# Sheet2.net
KiCad netlist of a schematic drawn in Altium Designer
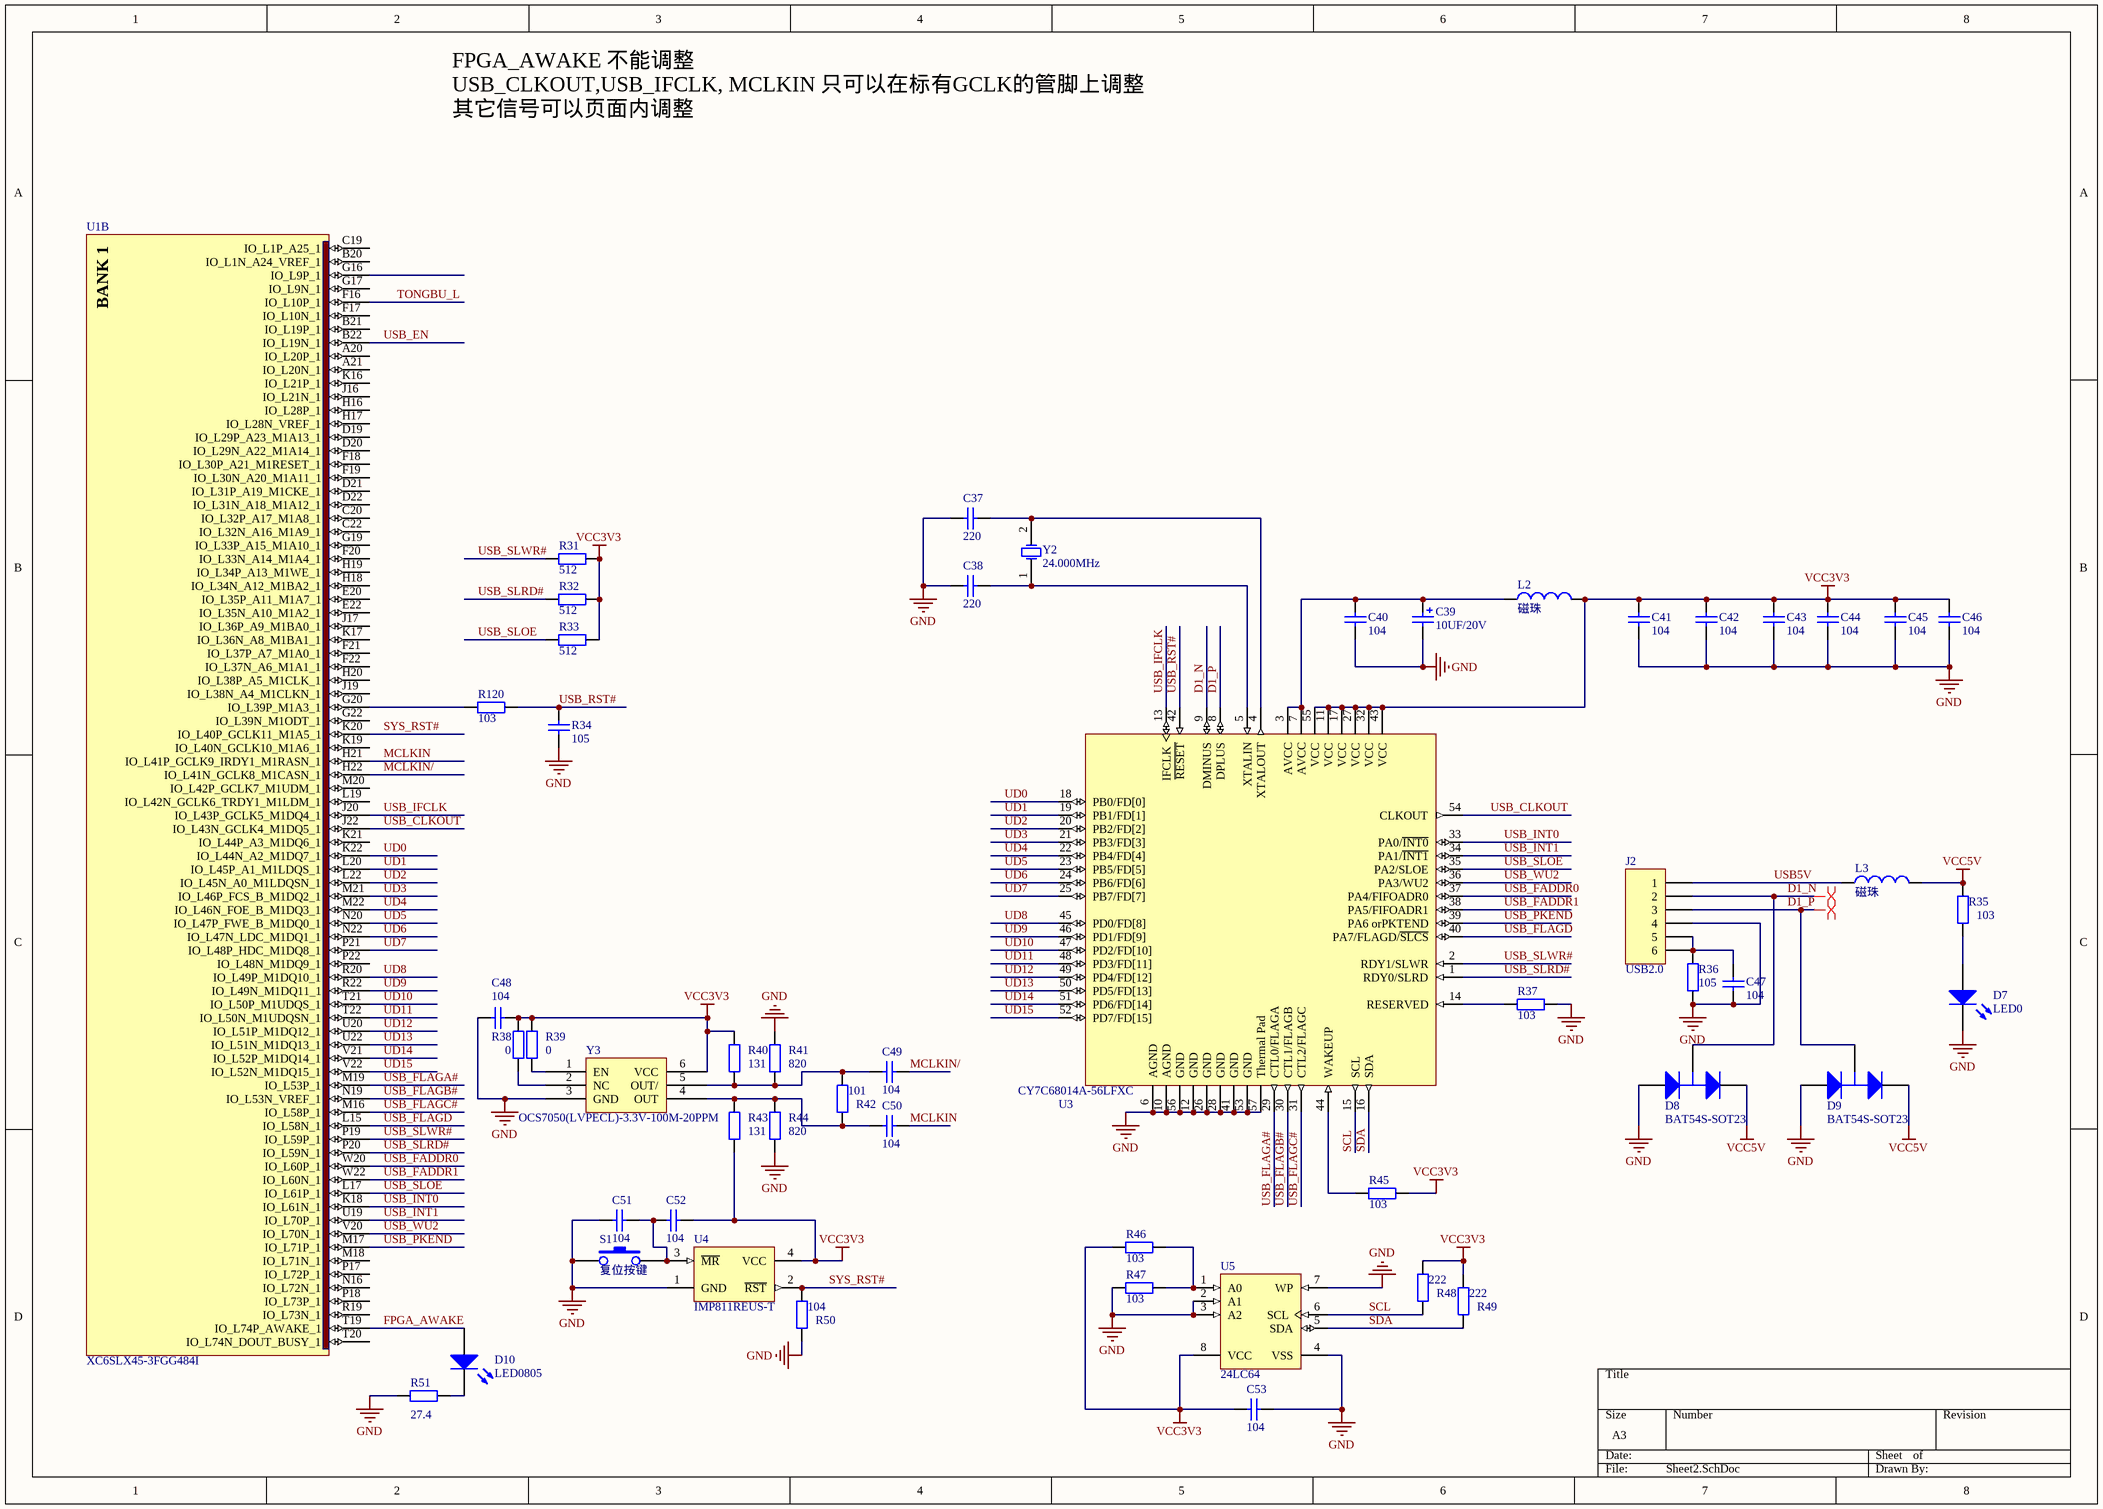
[diagram p0: Sheet2.SchDoc]

(export (version "E")
  (design (tool "Eeschema 10.0.6"))
  (components
    (comp (ref "C37")
      (value "220")
      (footprint "0402")
      (description "Capacitor")
      (fields (field (name "PUBLISHER") "Altium Limited"))
      (libsource (lib "Miscellaneous Devices") (part "Cap"))
    )
    (comp (ref "C38")
      (value "220")
      (footprint "0402")
      (description "Capacitor")
      (fields (field (name "PUBLISHER") "Altium Limited"))
      (libsource (lib "Miscellaneous Devices") (part "Cap"))
    )
    (comp (ref "C39")
      (value "10UF/20V")
      (footprint "CAP-B")
      (description "Polarized Capacitor (Axial)")
      (fields (field (name "PUBLISHER") "Altium Limited"))
      (libsource (lib "Miscellaneous Devices") (part "Cap Pol2"))
    )
    (comp (ref "C40")
      (value "104")
      (footprint "0402")
      (description "Capacitor")
      (fields (field (name "PUBLISHER") "Altium Limited"))
      (libsource (lib "Miscellaneous Devices") (part "Cap"))
    )
    (comp (ref "C41")
      (value "104")
      (footprint "0402")
      (description "Capacitor")
      (fields (field (name "PUBLISHER") "Altium Limited"))
      (libsource (lib "Miscellaneous Devices") (part "Cap"))
    )
    (comp (ref "C42")
      (value "104")
      (footprint "0402")
      (description "Capacitor")
      (fields (field (name "PUBLISHER") "Altium Limited"))
      (libsource (lib "Miscellaneous Devices") (part "Cap"))
    )
    (comp (ref "C43")
      (value "104")
      (footprint "0402")
      (description "Capacitor")
      (fields (field (name "PUBLISHER") "Altium Limited"))
      (libsource (lib "Miscellaneous Devices") (part "Cap"))
    )
    (comp (ref "C44")
      (value "104")
      (footprint "0402")
      (description "Capacitor")
      (fields (field (name "PUBLISHER") "Altium Limited"))
      (libsource (lib "Miscellaneous Devices") (part "Cap"))
    )
    (comp (ref "C45")
      (value "104")
      (footprint "0402")
      (description "Capacitor")
      (fields (field (name "PUBLISHER") "Altium Limited"))
      (libsource (lib "Miscellaneous Devices") (part "Cap"))
    )
    (comp (ref "C46")
      (value "104")
      (footprint "0402")
      (description "Capacitor")
      (fields (field (name "PUBLISHER") "Altium Limited"))
      (libsource (lib "Miscellaneous Devices") (part "Cap"))
    )
    (comp (ref "C47")
      (value "104")
      (footprint "0402")
      (description "Capacitor")
      (fields (field (name "PUBLISHER") "Altium Limited"))
      (libsource (lib "Miscellaneous Devices") (part "Cap"))
    )
    (comp (ref "C48")
      (value "104")
      (footprint "0402")
      (description "Capacitor")
      (fields (field (name "PUBLISHER") "Altium Limited"))
      (libsource (lib "Miscellaneous Devices") (part "Cap"))
    )
    (comp (ref "C49")
      (value "104")
      (footprint "0402")
      (description "Capacitor")
      (fields (field (name "PUBLISHER") "Altium Limited"))
      (libsource (lib "Miscellaneous Devices") (part "Cap"))
    )
    (comp (ref "C50")
      (value "104")
      (footprint "0402")
      (description "Capacitor")
      (fields (field (name "PUBLISHER") "Altium Limited"))
      (libsource (lib "Miscellaneous Devices") (part "Cap"))
    )
    (comp (ref "C51")
      (value "104")
      (footprint "0402")
      (description "Capacitor")
      (fields (field (name "PUBLISHER") "Altium Limited"))
      (libsource (lib "Miscellaneous Devices") (part "Cap"))
    )
    (comp (ref "C52")
      (value "104")
      (footprint "0402")
      (description "Capacitor")
      (fields (field (name "PUBLISHER") "Altium Limited"))
      (libsource (lib "Miscellaneous Devices") (part "Cap"))
    )
    (comp (ref "C53")
      (value "104")
      (footprint "0402")
      (description "Capacitor")
      (fields (field (name "PUBLISHER") "Altium Limited"))
      (libsource (lib "Miscellaneous Devices") (part "Cap"))
    )
    (comp (ref "D7")
      (value "LED0")
      (footprint "0805LED")
      (description "Typical INFRARED GaAs LED")
      (fields (field (name "PUBLISHER") "Altium Limited"))
      (libsource (lib "Miscellaneous Devices") (part "LED0"))
    )
    (comp (ref "D8")
      (value "BAT54S-SOT23")
      (footprint "SOT23-3L")
      (description "Silicon Switching Diode Array for High-Speed Switching")
      (fields (field (name "PUBLISHER") "Altium Limited"))
      (libsource (lib "Infineon Discrete Diode") (part "BAV99"))
    )
    (comp (ref "D9")
      (value "BAT54S-SOT23")
      (footprint "SOT23-3L")
      (description "Silicon Switching Diode Array for High-Speed Switching")
      (fields (field (name "PUBLISHER") "Altium Limited"))
      (libsource (lib "Infineon Discrete Diode") (part "BAV99"))
    )
    (comp (ref "D10")
      (value "LED0805")
      (footprint "0805LED")
      (description "Typical INFRARED GaAs LED")
      (fields (field (name "PUBLISHER") "Altium Limited"))
      (libsource (lib "Miscellaneous Devices") (part "LED0"))
    )
    (comp (ref "J2")
      (value "USB2.0")
      (footprint "USB-B")
      (description "Header, 6-Pin")
      (fields (field (name "PUBLISHER") "Altium Limited"))
      (libsource (lib "Miscellaneous Connectors") (part "Header 6"))
    )
    (comp (ref "L2")
      (value "磁珠")
      (footprint "1206A")
      (description "Inductor")
      (fields (field (name "PUBLISHER") "Altium Limited"))
      (libsource (lib "Miscellaneous Devices") (part "Inductor"))
    )
    (comp (ref "L3")
      (value "磁珠")
      (footprint "1206A")
      (description "Inductor")
      (fields (field (name "PUBLISHER") "Altium Limited"))
      (libsource (lib "Miscellaneous Devices") (part "Inductor"))
    )
    (comp (ref "R31")
      (value "512")
      (footprint "0603")
      (description "Resistor")
      (fields (field (name "PUBLISHER") "Altium Limited"))
      (libsource (lib "") (part "Res2_3"))
    )
    (comp (ref "R32")
      (value "512")
      (footprint "0603")
      (description "Resistor")
      (fields (field (name "PUBLISHER") "Altium Limited"))
      (libsource (lib "") (part "Res2_3"))
    )
    (comp (ref "R33")
      (value "512")
      (footprint "0603")
      (description "Resistor")
      (fields (field (name "PUBLISHER") "Altium Limited"))
      (libsource (lib "") (part "Res2_3"))
    )
    (comp (ref "R34")
      (value "105")
      (footprint "0603X")
      (description "Capacitor")
      (fields (field (name "PUBLISHER") "Altium Limited"))
      (libsource (lib "Miscellaneous Devices") (part "Cap"))
    )
    (comp (ref "R35")
      (value "103")
      (footprint "0603")
      (description "Resistor")
      (fields (field (name "PUBLISHER") "Altium Limited"))
      (libsource (lib "") (part "Res2_2"))
    )
    (comp (ref "R36")
      (value "105")
      (footprint "0603")
      (description "Resistor")
      (fields (field (name "PUBLISHER") "Altium Limited"))
      (libsource (lib "") (part "Res2_2"))
    )
    (comp (ref "R37")
      (value "103")
      (footprint "0603")
      (description "Resistor")
      (fields (field (name "PUBLISHER") "Altium Limited"))
      (libsource (lib "Miscellaneous Devices") (part "Res2"))
    )
    (comp (ref "R38")
      (value "0")
      (footprint "0603")
      (description "Resistor")
      (fields (field (name "PUBLISHER") "Altium Limited"))
      (libsource (lib "") (part "Res2_1"))
    )
    (comp (ref "R39")
      (value "0")
      (footprint "0603")
      (description "Resistor")
      (fields (field (name "PUBLISHER") "Altium Limited"))
      (libsource (lib "") (part "Res2_1"))
    )
    (comp (ref "R40")
      (value "131")
      (footprint "0603")
      (description "Resistor")
      (fields (field (name "PUBLISHER") "Altium Limited"))
      (libsource (lib "") (part "Res2_2"))
    )
    (comp (ref "R41")
      (value "820")
      (footprint "0603")
      (description "Resistor")
      (fields (field (name "PUBLISHER") "Altium Limited"))
      (libsource (lib "") (part "Res2_2"))
    )
    (comp (ref "R42")
      (value "101")
      (footprint "0603")
      (description "Resistor")
      (fields (field (name "PUBLISHER") "Altium Limited"))
      (libsource (lib "") (part "Res2_2"))
    )
    (comp (ref "R43")
      (value "131")
      (footprint "0603")
      (description "Resistor")
      (fields (field (name "PUBLISHER") "Altium Limited"))
      (libsource (lib "") (part "Res2_2"))
    )
    (comp (ref "R44")
      (value "820")
      (footprint "0603")
      (description "Resistor")
      (fields (field (name "PUBLISHER") "Altium Limited"))
      (libsource (lib "") (part "Res2_2"))
    )
    (comp (ref "R45")
      (value "103")
      (footprint "0603")
      (description "Resistor")
      (fields (field (name "PUBLISHER") "Altium Limited"))
      (libsource (lib "") (part "Res2_3"))
    )
    (comp (ref "R46")
      (value "103")
      (footprint "0603")
      (description "Resistor")
      (fields (field (name "PUBLISHER") "Altium Limited"))
      (libsource (lib "") (part "Res2_3"))
    )
    (comp (ref "R47")
      (value "103")
      (footprint "0603")
      (description "Resistor")
      (fields (field (name "PUBLISHER") "Altium Limited"))
      (libsource (lib "") (part "Res2_3"))
    )
    (comp (ref "R48")
      (value "222")
      (footprint "0603")
      (description "Resistor")
      (fields (field (name "PUBLISHER") "Altium Limited"))
      (libsource (lib "") (part "Res2_1"))
    )
    (comp (ref "R49")
      (value "222")
      (footprint "0603")
      (description "Resistor")
      (fields (field (name "PUBLISHER") "Altium Limited"))
      (libsource (lib "") (part "Res2_1"))
    )
    (comp (ref "R50")
      (value "104")
      (footprint "0603")
      (description "Resistor")
      (fields (field (name "PUBLISHER") "Altium Limited"))
      (libsource (lib "") (part "Res2_2"))
    )
    (comp (ref "R51")
      (value "27.4")
      (footprint "0603")
      (description "Resistor")
      (fields (field (name "PUBLISHER") "Altium Limited"))
      (libsource (lib "Miscellaneous Devices") (part "Res2"))
    )
    (comp (ref "R120")
      (value "103")
      (footprint "0603")
      (description "Resistor")
      (fields (field (name "PUBLISHER") "Altium Limited"))
      (libsource (lib "") (part "Res2_3"))
    )
    (comp (ref "S1") (value "复位按键") (footprint "RESETKEY") (libsource (lib "*") (part "SW-PB")))
    (comp (ref "U1")
      (value "XC6SLX45-3FGG484I")
      (footprint "FGG484")
      (fields (field (name "PUBLISHER") "Altium Limited"))
      (libsource (lib "Xilinx Spartan-6") (part "XC6SLX45-3FGG484I"))
    )
    (comp (ref "U3")
      (value "CY7C68014A-56LFXC")
      (footprint "LF56A_N")
      (fields (field (name "PUBLISHER") "Altium Limited"))
      (libsource (lib "Cypress USB High-Speed") (part "CY7C68014A-56LFXC"))
    )
    (comp (ref "U4")
      (value "IMP811REUS-T")
      (footprint "SOT-143")
      (description "4-Pin µP Voltage Monitors with Manual Reset Input")
      (fields (field (name "PUBLISHER") "Altium Limited"))
      (libsource (lib "Maxim Power Mgt Supervisory Circuit") (part "MAX811-EUS-T"))
    )
    (comp (ref "U5")
      (value "24LC64")
      (footprint "SMD8XX")
      (description "2Kbit, 400kHz, 2.5V, I2C Serial EEPROM, 8-Pin SOIC 150mil, Industrial Temperature")
      (fields (field (name "PUBLISHER") "Altium Limited"))
      (libsource (lib "Microchip Memory I2C Serial EEPROM") (part "24LC02B-I/SN"))
    )
    (comp (ref "Y2")
      (value "24.000MHz")
      (footprint "CRYSTAL_2")
      (description "Crystal Oscillator")
      (fields (field (name "PUBLISHER") "Altium Limited"))
      (libsource (lib "Miscellaneous Devices") (part "XTAL"))
    )
    (comp (ref "Y3")
      (value "OCS7050(LVPECL)-3.3V-100M-20PPM")
      (footprint "CCPD-940X-033")
      (libsource (lib "Schlib1") (part "Component_1"))
    )
  )
  (nets
    (net (code "1") (name "/D1_N") (class "Default")
      (node (ref "D8") (pin "3") (pinfunction "C_3") (pintype "passive"))
      (node (ref "J2") (pin "2") (pinfunction "2_2") (pintype "passive"))
      (node (ref "U3") (pin "9") (pinfunction "DMINUS_9") (pintype "bidirectional"))
    )
    (net (code "2") (name "/D1_P") (class "Default")
      (node (ref "D9") (pin "3") (pinfunction "C_3") (pintype "passive"))
      (node (ref "J2") (pin "3") (pinfunction "3_3") (pintype "passive"))
      (node (ref "U3") (pin "8") (pinfunction "DPLUS_8") (pintype "bidirectional"))
    )
    (net (code "3") (name "/FPGA_AWAKE") (class "Default")
      (node (ref "D10") (pin "1") (pinfunction "A_1") (pintype "passive"))
      (node (ref "U1") (pin "T19") (pinfunction "IO_L74P_AWAKE_1_T19") (pintype "bidirectional"))
    )
    (net (code "4") (name "/MCLKIN") (class "Default")
      (node (ref "C50") (pin "2") (pinfunction "2_2") (pintype "passive"))
      (node (ref "U1") (pin "H21") (pinfunction "IO_L41P_GCLK9_IRDY1_M1RASN_1_H21") (pintype "bidirectional"))
    )
    (net (code "5") (name "/MCLKIN{slash}") (class "Default")
      (node (ref "C49") (pin "2") (pinfunction "2_2") (pintype "passive"))
      (node (ref "U1") (pin "H22") (pinfunction "IO_L41N_GCLK8_M1CASN_1_H22") (pintype "bidirectional"))
    )
    (net (code "6") (name "/SCL") (class "Default")
      (node (ref "R48") (pin "2") (pinfunction "2_2") (pintype "passive"))
      (node (ref "U3") (pin "15") (pinfunction "SCL_15") (pintype "output"))
      (node (ref "U5") (pin "6") (pinfunction "SCL_6") (pintype "input"))
    )
    (net (code "7") (name "/SDA") (class "Default")
      (node (ref "R49") (pin "2") (pinfunction "2_2") (pintype "passive"))
      (node (ref "U3") (pin "16") (pinfunction "SDA_16") (pintype "output"))
      (node (ref "U5") (pin "5") (pinfunction "SDA_5") (pintype "bidirectional"))
    )
    (net (code "8") (name "/SYS_RST#") (class "Default")
      (node (ref "R50") (pin "2") (pinfunction "2_2") (pintype "passive"))
      (node (ref "U1") (pin "K20") (pinfunction "IO_L40P_GCLK11_M1A5_1_K20") (pintype "bidirectional"))
      (node (ref "U4") (pin "2") (pinfunction "~{RST}_2") (pintype "output"))
    )
    (net (code "9") (name "/TONGBU_L") (class "Default")
      (node (ref "U1") (pin "F16") (pinfunction "IO_L10P_1_F16") (pintype "bidirectional"))
    )
    (net (code "10") (name "/UD0") (class "Default")
      (node (ref "U1") (pin "K22") (pinfunction "IO_L44N_A2_M1DQ7_1_K22") (pintype "bidirectional"))
      (node (ref "U3") (pin "18") (pinfunction "PB0/FD[0]_18") (pintype "bidirectional"))
    )
    (net (code "11") (name "/UD1") (class "Default")
      (node (ref "U1") (pin "L20") (pinfunction "IO_L45P_A1_M1LDQS_1_L20") (pintype "bidirectional"))
      (node (ref "U3") (pin "19") (pinfunction "PB1/FD[1]_19") (pintype "bidirectional"))
    )
    (net (code "12") (name "/UD2") (class "Default")
      (node (ref "U1") (pin "L22") (pinfunction "IO_L45N_A0_M1LDQSN_1_L22") (pintype "bidirectional"))
      (node (ref "U3") (pin "20") (pinfunction "PB2/FD[2]_20") (pintype "bidirectional"))
    )
    (net (code "13") (name "/UD3") (class "Default")
      (node (ref "U1") (pin "M21") (pinfunction "IO_L46P_FCS_B_M1DQ2_1_M21") (pintype "bidirectional"))
      (node (ref "U3") (pin "21") (pinfunction "PB3/FD[3]_21") (pintype "bidirectional"))
    )
    (net (code "14") (name "/UD4") (class "Default")
      (node (ref "U1") (pin "M22") (pinfunction "IO_L46N_FOE_B_M1DQ3_1_M22") (pintype "bidirectional"))
      (node (ref "U3") (pin "22") (pinfunction "PB4/FD[4]_22") (pintype "bidirectional"))
    )
    (net (code "15") (name "/UD5") (class "Default")
      (node (ref "U1") (pin "N20") (pinfunction "IO_L47P_FWE_B_M1DQ0_1_N20") (pintype "bidirectional"))
      (node (ref "U3") (pin "23") (pinfunction "PB5/FD[5]_23") (pintype "bidirectional"))
    )
    (net (code "16") (name "/UD6") (class "Default")
      (node (ref "U1") (pin "N22") (pinfunction "IO_L47N_LDC_M1DQ1_1_N22") (pintype "bidirectional"))
      (node (ref "U3") (pin "24") (pinfunction "PB6/FD[6]_24") (pintype "bidirectional"))
    )
    (net (code "17") (name "/UD7") (class "Default")
      (node (ref "U1") (pin "P21") (pinfunction "IO_L48P_HDC_M1DQ8_1_P21") (pintype "bidirectional"))
      (node (ref "U3") (pin "25") (pinfunction "PB7/FD[7]_25") (pintype "bidirectional"))
    )
    (net (code "18") (name "/UD8") (class "Default")
      (node (ref "U1") (pin "R20") (pinfunction "IO_L49P_M1DQ10_1_R20") (pintype "bidirectional"))
      (node (ref "U3") (pin "45") (pinfunction "PD0/FD[8]_45") (pintype "bidirectional"))
    )
    (net (code "19") (name "/UD9") (class "Default")
      (node (ref "U1") (pin "R22") (pinfunction "IO_L49N_M1DQ11_1_R22") (pintype "bidirectional"))
      (node (ref "U3") (pin "46") (pinfunction "PD1/FD[9]_46") (pintype "bidirectional"))
    )
    (net (code "20") (name "/UD10") (class "Default")
      (node (ref "U1") (pin "T21") (pinfunction "IO_L50P_M1UDQS_1_T21") (pintype "bidirectional"))
      (node (ref "U3") (pin "47") (pinfunction "PD2/FD[10]_47") (pintype "bidirectional"))
    )
    (net (code "21") (name "/UD11") (class "Default")
      (node (ref "U1") (pin "T22") (pinfunction "IO_L50N_M1UDQSN_1_T22") (pintype "bidirectional"))
      (node (ref "U3") (pin "48") (pinfunction "PD3/FD[11]_48") (pintype "bidirectional"))
    )
    (net (code "22") (name "/UD12") (class "Default")
      (node (ref "U1") (pin "U20") (pinfunction "IO_L51P_M1DQ12_1_U20") (pintype "bidirectional"))
      (node (ref "U3") (pin "49") (pinfunction "PD4/FD[12]_49") (pintype "bidirectional"))
    )
    (net (code "23") (name "/UD13") (class "Default")
      (node (ref "U1") (pin "U22") (pinfunction "IO_L51N_M1DQ13_1_U22") (pintype "bidirectional"))
      (node (ref "U3") (pin "50") (pinfunction "PD5/FD[13]_50") (pintype "bidirectional"))
    )
    (net (code "24") (name "/UD14") (class "Default")
      (node (ref "U1") (pin "V21") (pinfunction "IO_L52P_M1DQ14_1_V21") (pintype "bidirectional"))
      (node (ref "U3") (pin "51") (pinfunction "PD6/FD[14]_51") (pintype "bidirectional"))
    )
    (net (code "25") (name "/UD15") (class "Default")
      (node (ref "U1") (pin "V22") (pinfunction "IO_L52N_M1DQ15_1_V22") (pintype "bidirectional"))
      (node (ref "U3") (pin "52") (pinfunction "PD7/FD[15]_52") (pintype "bidirectional"))
    )
    (net (code "26") (name "/USB5V") (class "Default")
      (node (ref "J2") (pin "1") (pinfunction "1_1") (pintype "passive"))
      (node (ref "L3") (pin "1") (pinfunction "1_1") (pintype "passive"))
    )
    (net (code "27") (name "/USB_CLKOUT") (class "Default")
      (node (ref "U1") (pin "J22") (pinfunction "IO_L43N_GCLK4_M1DQ5_1_J22") (pintype "bidirectional"))
      (node (ref "U3") (pin "54") (pinfunction "CLKOUT_54") (pintype "output"))
    )
    (net (code "28") (name "/USB_EN") (class "Default")
      (node (ref "U1") (pin "B22") (pinfunction "IO_L19N_1_B22") (pintype "bidirectional"))
    )
    (net (code "29") (name "/USB_FADDR0") (class "Default")
      (node (ref "U1") (pin "W20") (pinfunction "IO_L60P_1_W20") (pintype "bidirectional"))
      (node (ref "U3") (pin "37") (pinfunction "PA4/FIFOADR0_37") (pintype "bidirectional"))
    )
    (net (code "30") (name "/USB_FADDR1") (class "Default")
      (node (ref "U1") (pin "W22") (pinfunction "IO_L60N_1_W22") (pintype "bidirectional"))
      (node (ref "U3") (pin "38") (pinfunction "PA5/FIFOADR1_38") (pintype "bidirectional"))
    )
    (net (code "31") (name "/USB_FLAGA#") (class "Default")
      (node (ref "U1") (pin "M19") (pinfunction "IO_L53P_1_M19") (pintype "bidirectional"))
      (node (ref "U3") (pin "29") (pinfunction "CTL0/FLAGA_29") (pintype "output"))
    )
    (net (code "32") (name "/USB_FLAGB#") (class "Default")
      (node (ref "U1") (pin "N19") (pinfunction "IO_L53N_VREF_1_N19") (pintype "bidirectional"))
      (node (ref "U3") (pin "30") (pinfunction "CTL1/FLAGB_30") (pintype "output"))
    )
    (net (code "33") (name "/USB_FLAGC#") (class "Default")
      (node (ref "U1") (pin "M16") (pinfunction "IO_L58P_1_M16") (pintype "bidirectional"))
      (node (ref "U3") (pin "31") (pinfunction "CTL2/FLAGC_31") (pintype "output"))
    )
    (net (code "34") (name "/USB_FLAGD") (class "Default")
      (node (ref "U1") (pin "L15") (pinfunction "IO_L58N_1_L15") (pintype "bidirectional"))
      (node (ref "U3") (pin "40") (pinfunction "PA7/FLAGD/~{SLCS}_40") (pintype "bidirectional"))
    )
    (net (code "35") (name "/USB_IFCLK") (class "Default")
      (node (ref "U1") (pin "J20") (pinfunction "IO_L43P_GCLK5_M1DQ4_1_J20") (pintype "bidirectional"))
      (node (ref "U3") (pin "13") (pinfunction "IFCLK_13") (pintype "bidirectional"))
    )
    (net (code "36") (name "/USB_INT0") (class "Default")
      (node (ref "U1") (pin "K18") (pinfunction "IO_L61N_1_K18") (pintype "bidirectional"))
      (node (ref "U3") (pin "33") (pinfunction "PA0/~{INT0}_33") (pintype "bidirectional"))
    )
    (net (code "37") (name "/USB_INT1") (class "Default")
      (node (ref "U1") (pin "U19") (pinfunction "IO_L70P_1_U19") (pintype "bidirectional"))
      (node (ref "U3") (pin "34") (pinfunction "PA1/~{INT1}_34") (pintype "bidirectional"))
    )
    (net (code "38") (name "/USB_PKEND") (class "Default")
      (node (ref "U1") (pin "M17") (pinfunction "IO_L71P_1_M17") (pintype "bidirectional"))
      (node (ref "U3") (pin "39") (pinfunction "PA6_orPKTEND_39") (pintype "bidirectional"))
    )
    (net (code "39") (name "/USB_RST#") (class "Default")
      (node (ref "R120") (pin "1") (pinfunction "1_1") (pintype "passive"))
      (node (ref "R34") (pin "2") (pinfunction "2_2") (pintype "passive"))
      (node (ref "U3") (pin "42") (pinfunction "~{RESET}_42") (pintype "input"))
    )
    (net (code "40") (name "/USB_SLOE") (class "Default")
      (node (ref "R33") (pin "2") (pinfunction "2_2") (pintype "passive"))
      (node (ref "U1") (pin "L17") (pinfunction "IO_L61P_1_L17") (pintype "bidirectional"))
      (node (ref "U3") (pin "35") (pinfunction "PA2/SLOE_35") (pintype "bidirectional"))
    )
    (net (code "41") (name "/USB_SLRD#") (class "Default")
      (node (ref "R32") (pin "2") (pinfunction "2_2") (pintype "passive"))
      (node (ref "U1") (pin "P20") (pinfunction "IO_L59N_1_P20") (pintype "bidirectional"))
      (node (ref "U3") (pin "1") (pinfunction "RDY0/SLRD_1") (pintype "input"))
    )
    (net (code "42") (name "/USB_SLWR#") (class "Default")
      (node (ref "R31") (pin "2") (pinfunction "2_2") (pintype "passive"))
      (node (ref "U1") (pin "P19") (pinfunction "IO_L59P_1_P19") (pintype "bidirectional"))
      (node (ref "U3") (pin "2") (pinfunction "RDY1/SLWR_2") (pintype "input"))
    )
    (net (code "43") (name "/USB_WU2") (class "Default")
      (node (ref "U1") (pin "V20") (pinfunction "IO_L70N_1_V20") (pintype "bidirectional"))
      (node (ref "U3") (pin "36") (pinfunction "PA3/WU2_36") (pintype "bidirectional"))
    )
    (net (code "44") (name "GND") (class "Default")
      (node (ref "C37") (pin "1") (pinfunction "1_1") (pintype "passive"))
      (node (ref "C38") (pin "1") (pinfunction "1_1") (pintype "passive"))
      (node (ref "C39") (pin "2") (pinfunction "2_2") (pintype "passive"))
      (node (ref "C40") (pin "1") (pinfunction "1_1") (pintype "passive"))
      (node (ref "C41") (pin "1") (pinfunction "1_1") (pintype "passive"))
      (node (ref "C42") (pin "1") (pinfunction "1_1") (pintype "passive"))
      (node (ref "C43") (pin "1") (pinfunction "1_1") (pintype "passive"))
      (node (ref "C44") (pin "1") (pinfunction "1_1") (pintype "passive"))
      (node (ref "C45") (pin "1") (pinfunction "1_1") (pintype "passive"))
      (node (ref "C46") (pin "1") (pinfunction "1_1") (pintype "passive"))
      (node (ref "C47") (pin "2") (pinfunction "2_2") (pintype "passive"))
      (node (ref "C48") (pin "2") (pinfunction "2_2") (pintype "passive"))
      (node (ref "C51") (pin "2") (pinfunction "2_2") (pintype "passive"))
      (node (ref "C53") (pin "1") (pinfunction "1_1") (pintype "passive"))
      (node (ref "D7") (pin "2") (pinfunction "K_2") (pintype "passive"))
      (node (ref "D8") (pin "1") (pinfunction "A_1") (pintype "passive"))
      (node (ref "D9") (pin "1") (pinfunction "A_1") (pintype "passive"))
      (node (ref "J2") (pin "4") (pinfunction "4_4") (pintype "passive"))
      (node (ref "R34") (pin "1") (pinfunction "1_1") (pintype "passive"))
      (node (ref "R36") (pin "1") (pinfunction "1_1") (pintype "passive"))
      (node (ref "R37") (pin "2") (pinfunction "2_2") (pintype "passive"))
      (node (ref "R41") (pin "2") (pinfunction "2_2") (pintype "passive"))
      (node (ref "R44") (pin "1") (pinfunction "1_1") (pintype "passive"))
      (node (ref "R47") (pin "2") (pinfunction "2_2") (pintype "passive"))
      (node (ref "R50") (pin "1") (pinfunction "1_1") (pintype "passive"))
      (node (ref "R51") (pin "1") (pinfunction "1_1") (pintype "passive"))
      (node (ref "S1") (pin "1") (pinfunction "1_1") (pintype "passive"))
      (node (ref "U3") (pin "10") (pinfunction "AGND_10") (pintype "power_in"))
      (node (ref "U3") (pin "12") (pinfunction "GND_12") (pintype "power_in"))
      (node (ref "U3") (pin "26") (pinfunction "GND_26") (pintype "power_in"))
      (node (ref "U3") (pin "28") (pinfunction "GND_28") (pintype "power_in"))
      (node (ref "U3") (pin "41") (pinfunction "GND_41") (pintype "power_in"))
      (node (ref "U3") (pin "53") (pinfunction "GND_53") (pintype "power_in"))
      (node (ref "U3") (pin "56") (pinfunction "GND_56") (pintype "power_in"))
      (node (ref "U3") (pin "57") (pinfunction "Thermal_Pad_57") (pintype "power_in"))
      (node (ref "U3") (pin "6") (pinfunction "AGND_6") (pintype "power_in"))
      (node (ref "U4") (pin "1") (pinfunction "GND_1") (pintype "power_in"))
      (node (ref "U5") (pin "2") (pinfunction "A1_2") (pintype "input"))
      (node (ref "U5") (pin "3") (pinfunction "A2_3") (pintype "input"))
      (node (ref "U5") (pin "4") (pinfunction "VSS_4") (pintype "power_in"))
      (node (ref "U5") (pin "7") (pinfunction "WP_7") (pintype "input"))
      (node (ref "Y3") (pin "3") (pinfunction "GND_3") (pintype "passive"))
    )
    (net (code "45") (name "Net-(C39-Pad1)") (class "Default")
      (node (ref "C39") (pin "1") (pinfunction "1_1") (pintype "passive"))
      (node (ref "C40") (pin "2") (pinfunction "2_2") (pintype "passive"))
      (node (ref "L2") (pin "1") (pinfunction "1_1") (pintype "passive"))
      (node (ref "U3") (pin "3") (pinfunction "AVCC_3") (pintype "power_in"))
      (node (ref "U3") (pin "7") (pinfunction "AVCC_7") (pintype "power_in"))
    )
    (net (code "46") (name "Net-(C47-Pad1)") (class "Default")
      (node (ref "C47") (pin "1") (pinfunction "1_1") (pintype "passive"))
      (node (ref "J2") (pin "5") (pinfunction "5_5") (pintype "passive"))
      (node (ref "J2") (pin "6") (pinfunction "6_6") (pintype "passive"))
      (node (ref "R36") (pin "2") (pinfunction "2_2") (pintype "passive"))
    )
    (net (code "47") (name "Net-(D7-A)") (class "Default")
      (node (ref "D7") (pin "1") (pinfunction "A_1") (pintype "passive"))
      (node (ref "R35") (pin "1") (pinfunction "1_1") (pintype "passive"))
    )
    (net (code "48") (name "Net-(D10-K)") (class "Default")
      (node (ref "D10") (pin "2") (pinfunction "K_2") (pintype "passive"))
      (node (ref "R51") (pin "2") (pinfunction "2_2") (pintype "passive"))
    )
    (net (code "49") (name "Net-(U1B-IO_L39P_M1A3_1)") (class "Default")
      (node (ref "R120") (pin "2") (pinfunction "2_2") (pintype "passive"))
      (node (ref "U1") (pin "G20") (pinfunction "IO_L39P_M1A3_1_G20") (pintype "bidirectional"))
    )
    (net (code "50") (name "Net-(U3-RESERVED)") (class "Default")
      (node (ref "R37") (pin "1") (pinfunction "1_1") (pintype "passive"))
      (node (ref "U3") (pin "14") (pinfunction "RESERVED_14") (pintype "input"))
    )
    (net (code "51") (name "Net-(U3-WAKEUP)") (class "Default")
      (node (ref "R45") (pin "2") (pinfunction "2_2") (pintype "passive"))
      (node (ref "U3") (pin "44") (pinfunction "WAKEUP_44") (pintype "input"))
    )
    (net (code "52") (name "Net-(U3-XTALIN)") (class "Default")
      (node (ref "C38") (pin "2") (pinfunction "2_2") (pintype "passive"))
      (node (ref "U3") (pin "5") (pinfunction "XTALIN_5") (pintype "input"))
      (node (ref "Y2") (pin "1") (pinfunction "OSC1_1") (pintype "passive"))
    )
    (net (code "53") (name "Net-(U3-XTALOUT)") (class "Default")
      (node (ref "C37") (pin "2") (pinfunction "2_2") (pintype "passive"))
      (node (ref "U3") (pin "4") (pinfunction "XTALOUT_4") (pintype "output"))
      (node (ref "Y2") (pin "2") (pinfunction "OSC2_2") (pintype "passive"))
    )
    (net (code "54") (name "Net-(U4-~{MR})") (class "Default")
      (node (ref "C51") (pin "1") (pinfunction "1_1") (pintype "passive"))
      (node (ref "C52") (pin "2") (pinfunction "2_2") (pintype "passive"))
      (node (ref "S1") (pin "2") (pinfunction "2_2") (pintype "passive"))
      (node (ref "U4") (pin "3") (pinfunction "~{MR}_3") (pintype "input"))
    )
    (net (code "55") (name "Net-(U5-A0)") (class "Default")
      (node (ref "R46") (pin "1") (pinfunction "1_1") (pintype "passive"))
      (node (ref "R47") (pin "1") (pinfunction "1_1") (pintype "passive"))
      (node (ref "U5") (pin "1") (pinfunction "A0_1") (pintype "input"))
    )
    (net (code "56") (name "Net-(Y3-EN)") (class "Default")
      (node (ref "R39") (pin "2") (pinfunction "2_2") (pintype "passive"))
      (node (ref "Y3") (pin "1") (pinfunction "EN_1") (pintype "passive"))
    )
    (net (code "57") (name "Net-(Y3-NC)") (class "Default")
      (node (ref "R38") (pin "2") (pinfunction "2_2") (pintype "passive"))
      (node (ref "Y3") (pin "2") (pinfunction "NC_2") (pintype "passive"))
    )
    (net (code "58") (name "Net-(Y3-OUT)") (class "Default")
      (node (ref "C50") (pin "1") (pinfunction "1_1") (pintype "passive"))
      (node (ref "R42") (pin "1") (pinfunction "1_1") (pintype "passive"))
      (node (ref "R43") (pin "2") (pinfunction "2_2") (pintype "passive"))
      (node (ref "R44") (pin "2") (pinfunction "2_2") (pintype "passive"))
      (node (ref "Y3") (pin "4") (pinfunction "OUT_4") (pintype "passive"))
    )
    (net (code "59") (name "Net-(Y3-OUT{slash})") (class "Default")
      (node (ref "C49") (pin "1") (pinfunction "1_1") (pintype "passive"))
      (node (ref "R40") (pin "1") (pinfunction "1_1") (pintype "passive"))
      (node (ref "R41") (pin "1") (pinfunction "1_1") (pintype "passive"))
      (node (ref "R42") (pin "2") (pinfunction "2_2") (pintype "passive"))
      (node (ref "Y3") (pin "5") (pinfunction "OUT/_5") (pintype "passive"))
    )
    (net (code "60") (name "VCC3V3") (class "Default")
      (node (ref "C41") (pin "2") (pinfunction "2_2") (pintype "passive"))
      (node (ref "C42") (pin "2") (pinfunction "2_2") (pintype "passive"))
      (node (ref "C43") (pin "2") (pinfunction "2_2") (pintype "passive"))
      (node (ref "C44") (pin "2") (pinfunction "2_2") (pintype "passive"))
      (node (ref "C45") (pin "2") (pinfunction "2_2") (pintype "passive"))
      (node (ref "C46") (pin "2") (pinfunction "2_2") (pintype "passive"))
      (node (ref "C48") (pin "1") (pinfunction "1_1") (pintype "passive"))
      (node (ref "C52") (pin "1") (pinfunction "1_1") (pintype "passive"))
      (node (ref "C53") (pin "2") (pinfunction "2_2") (pintype "passive"))
      (node (ref "L2") (pin "2") (pinfunction "2_2") (pintype "passive"))
      (node (ref "R31") (pin "1") (pinfunction "1_1") (pintype "passive"))
      (node (ref "R32") (pin "1") (pinfunction "1_1") (pintype "passive"))
      (node (ref "R33") (pin "1") (pinfunction "1_1") (pintype "passive"))
      (node (ref "R38") (pin "1") (pinfunction "1_1") (pintype "passive"))
      (node (ref "R39") (pin "1") (pinfunction "1_1") (pintype "passive"))
      (node (ref "R40") (pin "2") (pinfunction "2_2") (pintype "passive"))
      (node (ref "R43") (pin "1") (pinfunction "1_1") (pintype "passive"))
      (node (ref "R45") (pin "1") (pinfunction "1_1") (pintype "passive"))
      (node (ref "R46") (pin "2") (pinfunction "2_2") (pintype "passive"))
      (node (ref "R48") (pin "1") (pinfunction "1_1") (pintype "passive"))
      (node (ref "R49") (pin "1") (pinfunction "1_1") (pintype "passive"))
      (node (ref "U3") (pin "11") (pinfunction "VCC_11") (pintype "power_in"))
      (node (ref "U3") (pin "17") (pinfunction "VCC_17") (pintype "power_in"))
      (node (ref "U3") (pin "27") (pinfunction "VCC_27") (pintype "power_in"))
      (node (ref "U3") (pin "32") (pinfunction "VCC_32") (pintype "power_in"))
      (node (ref "U3") (pin "43") (pinfunction "VCC_43") (pintype "power_in"))
      (node (ref "U3") (pin "55") (pinfunction "VCC_55") (pintype "power_in"))
      (node (ref "U4") (pin "4") (pinfunction "VCC_4") (pintype "power_in"))
      (node (ref "U5") (pin "8") (pinfunction "VCC_8") (pintype "power_in"))
      (node (ref "Y3") (pin "6") (pinfunction "VCC_6") (pintype "passive"))
    )
    (net (code "61") (name "VCC5V") (class "Default")
      (node (ref "D8") (pin "2") (pinfunction "K_2") (pintype "passive"))
      (node (ref "D9") (pin "2") (pinfunction "K_2") (pintype "passive"))
      (node (ref "L3") (pin "2") (pinfunction "2_2") (pintype "passive"))
      (node (ref "R35") (pin "2") (pinfunction "2_2") (pintype "passive"))
    )
    (net (code "62") (name "unconnected-(U1B-IO_L1N_A24_VREF_1-PadB20)") (class "Default")
      (node (ref "U1") (pin "B20") (pinfunction "IO_L1N_A24_VREF_1_B20") (pintype "bidirectional"))
    )
    (net (code "63") (name "unconnected-(U1B-IO_L1P_A25_1-PadC19)") (class "Default")
      (node (ref "U1") (pin "C19") (pinfunction "IO_L1P_A25_1_C19") (pintype "bidirectional"))
    )
    (net (code "64") (name "unconnected-(U1B-IO_L9N_1-PadG17)") (class "Default")
      (node (ref "U1") (pin "G17") (pinfunction "IO_L9N_1_G17") (pintype "bidirectional"))
    )
    (net (code "65") (name "unconnected-(U1B-IO_L9P_1-PadG16)") (class "Default")
      (node (ref "U1") (pin "G16") (pinfunction "IO_L9P_1_G16") (pintype "bidirectional"))
    )
    (net (code "66") (name "unconnected-(U1B-IO_L10N_1-PadF17)") (class "Default")
      (node (ref "U1") (pin "F17") (pinfunction "IO_L10N_1_F17") (pintype "bidirectional"))
    )
    (net (code "67") (name "unconnected-(U1B-IO_L19P_1-PadB21)") (class "Default")
      (node (ref "U1") (pin "B21") (pinfunction "IO_L19P_1_B21") (pintype "bidirectional"))
    )
    (net (code "68") (name "unconnected-(U1B-IO_L20N_1-PadA21)") (class "Default")
      (node (ref "U1") (pin "A21") (pinfunction "IO_L20N_1_A21") (pintype "bidirectional"))
    )
    (net (code "69") (name "unconnected-(U1B-IO_L20P_1-PadA20)") (class "Default")
      (node (ref "U1") (pin "A20") (pinfunction "IO_L20P_1_A20") (pintype "bidirectional"))
    )
    (net (code "70") (name "unconnected-(U1B-IO_L21N_1-PadJ16)") (class "Default")
      (node (ref "U1") (pin "J16") (pinfunction "IO_L21N_1_J16") (pintype "bidirectional"))
    )
    (net (code "71") (name "unconnected-(U1B-IO_L21P_1-PadK16)") (class "Default")
      (node (ref "U1") (pin "K16") (pinfunction "IO_L21P_1_K16") (pintype "bidirectional"))
    )
    (net (code "72") (name "unconnected-(U1B-IO_L28N_VREF_1-PadH17)") (class "Default")
      (node (ref "U1") (pin "H17") (pinfunction "IO_L28N_VREF_1_H17") (pintype "bidirectional"))
    )
    (net (code "73") (name "unconnected-(U1B-IO_L28P_1-PadH16)") (class "Default")
      (node (ref "U1") (pin "H16") (pinfunction "IO_L28P_1_H16") (pintype "bidirectional"))
    )
    (net (code "74") (name "unconnected-(U1B-IO_L29N_A22_M1A14_1-PadD20)") (class "Default")
      (node (ref "U1") (pin "D20") (pinfunction "IO_L29N_A22_M1A14_1_D20") (pintype "bidirectional"))
    )
    (net (code "75") (name "unconnected-(U1B-IO_L29P_A23_M1A13_1-PadD19)") (class "Default")
      (node (ref "U1") (pin "D19") (pinfunction "IO_L29P_A23_M1A13_1_D19") (pintype "bidirectional"))
    )
    (net (code "76") (name "unconnected-(U1B-IO_L30N_A20_M1A11_1-PadF19)") (class "Default")
      (node (ref "U1") (pin "F19") (pinfunction "IO_L30N_A20_M1A11_1_F19") (pintype "bidirectional"))
    )
    (net (code "77") (name "unconnected-(U1B-IO_L30P_A21_M1RESET_1-PadF18)") (class "Default")
      (node (ref "U1") (pin "F18") (pinfunction "IO_L30P_A21_M1RESET_1_F18") (pintype "bidirectional"))
    )
    (net (code "78") (name "unconnected-(U1B-IO_L31N_A18_M1A12_1-PadD22)") (class "Default")
      (node (ref "U1") (pin "D22") (pinfunction "IO_L31N_A18_M1A12_1_D22") (pintype "bidirectional"))
    )
    (net (code "79") (name "unconnected-(U1B-IO_L31P_A19_M1CKE_1-PadD21)") (class "Default")
      (node (ref "U1") (pin "D21") (pinfunction "IO_L31P_A19_M1CKE_1_D21") (pintype "bidirectional"))
    )
    (net (code "80") (name "unconnected-(U1B-IO_L32N_A16_M1A9_1-PadC22)") (class "Default")
      (node (ref "U1") (pin "C22") (pinfunction "IO_L32N_A16_M1A9_1_C22") (pintype "bidirectional"))
    )
    (net (code "81") (name "unconnected-(U1B-IO_L32P_A17_M1A8_1-PadC20)") (class "Default")
      (node (ref "U1") (pin "C20") (pinfunction "IO_L32P_A17_M1A8_1_C20") (pintype "bidirectional"))
    )
    (net (code "82") (name "unconnected-(U1B-IO_L33N_A14_M1A4_1-PadF20)") (class "Default")
      (node (ref "U1") (pin "F20") (pinfunction "IO_L33N_A14_M1A4_1_F20") (pintype "bidirectional"))
    )
    (net (code "83") (name "unconnected-(U1B-IO_L33P_A15_M1A10_1-PadG19)") (class "Default")
      (node (ref "U1") (pin "G19") (pinfunction "IO_L33P_A15_M1A10_1_G19") (pintype "bidirectional"))
    )
    (net (code "84") (name "unconnected-(U1B-IO_L34N_A12_M1BA2_1-PadH18)") (class "Default")
      (node (ref "U1") (pin "H18") (pinfunction "IO_L34N_A12_M1BA2_1_H18") (pintype "bidirectional"))
    )
    (net (code "85") (name "unconnected-(U1B-IO_L34P_A13_M1WE_1-PadH19)") (class "Default")
      (node (ref "U1") (pin "H19") (pinfunction "IO_L34P_A13_M1WE_1_H19") (pintype "bidirectional"))
    )
    (net (code "86") (name "unconnected-(U1B-IO_L35N_A10_M1A2_1-PadE22)") (class "Default")
      (node (ref "U1") (pin "E22") (pinfunction "IO_L35N_A10_M1A2_1_E22") (pintype "bidirectional"))
    )
    (net (code "87") (name "unconnected-(U1B-IO_L35P_A11_M1A7_1-PadE20)") (class "Default")
      (node (ref "U1") (pin "E20") (pinfunction "IO_L35P_A11_M1A7_1_E20") (pintype "bidirectional"))
    )
    (net (code "88") (name "unconnected-(U1B-IO_L36N_A8_M1BA1_1-PadK17)") (class "Default")
      (node (ref "U1") (pin "K17") (pinfunction "IO_L36N_A8_M1BA1_1_K17") (pintype "bidirectional"))
    )
    (net (code "89") (name "unconnected-(U1B-IO_L36P_A9_M1BA0_1-PadJ17)") (class "Default")
      (node (ref "U1") (pin "J17") (pinfunction "IO_L36P_A9_M1BA0_1_J17") (pintype "bidirectional"))
    )
    (net (code "90") (name "unconnected-(U1B-IO_L37N_A6_M1A1_1-PadF22)") (class "Default")
      (node (ref "U1") (pin "F22") (pinfunction "IO_L37N_A6_M1A1_1_F22") (pintype "bidirectional"))
    )
    (net (code "91") (name "unconnected-(U1B-IO_L37P_A7_M1A0_1-PadF21)") (class "Default")
      (node (ref "U1") (pin "F21") (pinfunction "IO_L37P_A7_M1A0_1_F21") (pintype "bidirectional"))
    )
    (net (code "92") (name "unconnected-(U1B-IO_L38N_A4_M1CLKN_1-PadJ19)") (class "Default")
      (node (ref "U1") (pin "J19") (pinfunction "IO_L38N_A4_M1CLKN_1_J19") (pintype "bidirectional"))
    )
    (net (code "93") (name "unconnected-(U1B-IO_L38P_A5_M1CLK_1-PadH20)") (class "Default")
      (node (ref "U1") (pin "H20") (pinfunction "IO_L38P_A5_M1CLK_1_H20") (pintype "bidirectional"))
    )
    (net (code "94") (name "unconnected-(U1B-IO_L39N_M1ODT_1-PadG22)") (class "Default")
      (node (ref "U1") (pin "G22") (pinfunction "IO_L39N_M1ODT_1_G22") (pintype "bidirectional"))
    )
    (net (code "95") (name "unconnected-(U1B-IO_L40N_GCLK10_M1A6_1-PadK19)") (class "Default")
      (node (ref "U1") (pin "K19") (pinfunction "IO_L40N_GCLK10_M1A6_1_K19") (pintype "bidirectional"))
    )
    (net (code "96") (name "unconnected-(U1B-IO_L42N_GCLK6_TRDY1_M1LDM_1-PadL19)") (class "Default")
      (node (ref "U1") (pin "L19") (pinfunction "IO_L42N_GCLK6_TRDY1_M1LDM_1_L19") (pintype "bidirectional"))
    )
    (net (code "97") (name "unconnected-(U1B-IO_L42P_GCLK7_M1UDM_1-PadM20)") (class "Default")
      (node (ref "U1") (pin "M20") (pinfunction "IO_L42P_GCLK7_M1UDM_1_M20") (pintype "bidirectional"))
    )
    (net (code "98") (name "unconnected-(U1B-IO_L44P_A3_M1DQ6_1-PadK21)") (class "Default")
      (node (ref "U1") (pin "K21") (pinfunction "IO_L44P_A3_M1DQ6_1_K21") (pintype "bidirectional"))
    )
    (net (code "99") (name "unconnected-(U1B-IO_L48N_M1DQ9_1-PadP22)") (class "Default")
      (node (ref "U1") (pin "P22") (pinfunction "IO_L48N_M1DQ9_1_P22") (pintype "bidirectional"))
    )
    (net (code "100") (name "unconnected-(U1B-IO_L71N_1-PadM18)") (class "Default")
      (node (ref "U1") (pin "M18") (pinfunction "IO_L71N_1_M18") (pintype "bidirectional"))
    )
    (net (code "101") (name "unconnected-(U1B-IO_L72N_1-PadN16)") (class "Default")
      (node (ref "U1") (pin "N16") (pinfunction "IO_L72N_1_N16") (pintype "bidirectional"))
    )
    (net (code "102") (name "unconnected-(U1B-IO_L72P_1-PadP17)") (class "Default")
      (node (ref "U1") (pin "P17") (pinfunction "IO_L72P_1_P17") (pintype "bidirectional"))
    )
    (net (code "103") (name "unconnected-(U1B-IO_L73N_1-PadR19)") (class "Default")
      (node (ref "U1") (pin "R19") (pinfunction "IO_L73N_1_R19") (pintype "bidirectional"))
    )
    (net (code "104") (name "unconnected-(U1B-IO_L73P_1-PadP18)") (class "Default")
      (node (ref "U1") (pin "P18") (pinfunction "IO_L73P_1_P18") (pintype "bidirectional"))
    )
    (net (code "105") (name "unconnected-(U1B-IO_L74N_DOUT_BUSY_1-PadT20)") (class "Default")
      (node (ref "U1") (pin "T20") (pinfunction "IO_L74N_DOUT_BUSY_1_T20") (pintype "bidirectional"))
    )
  )
)
